# BB8_Head.net
KiCad netlist of a schematic drawn in EAGLE
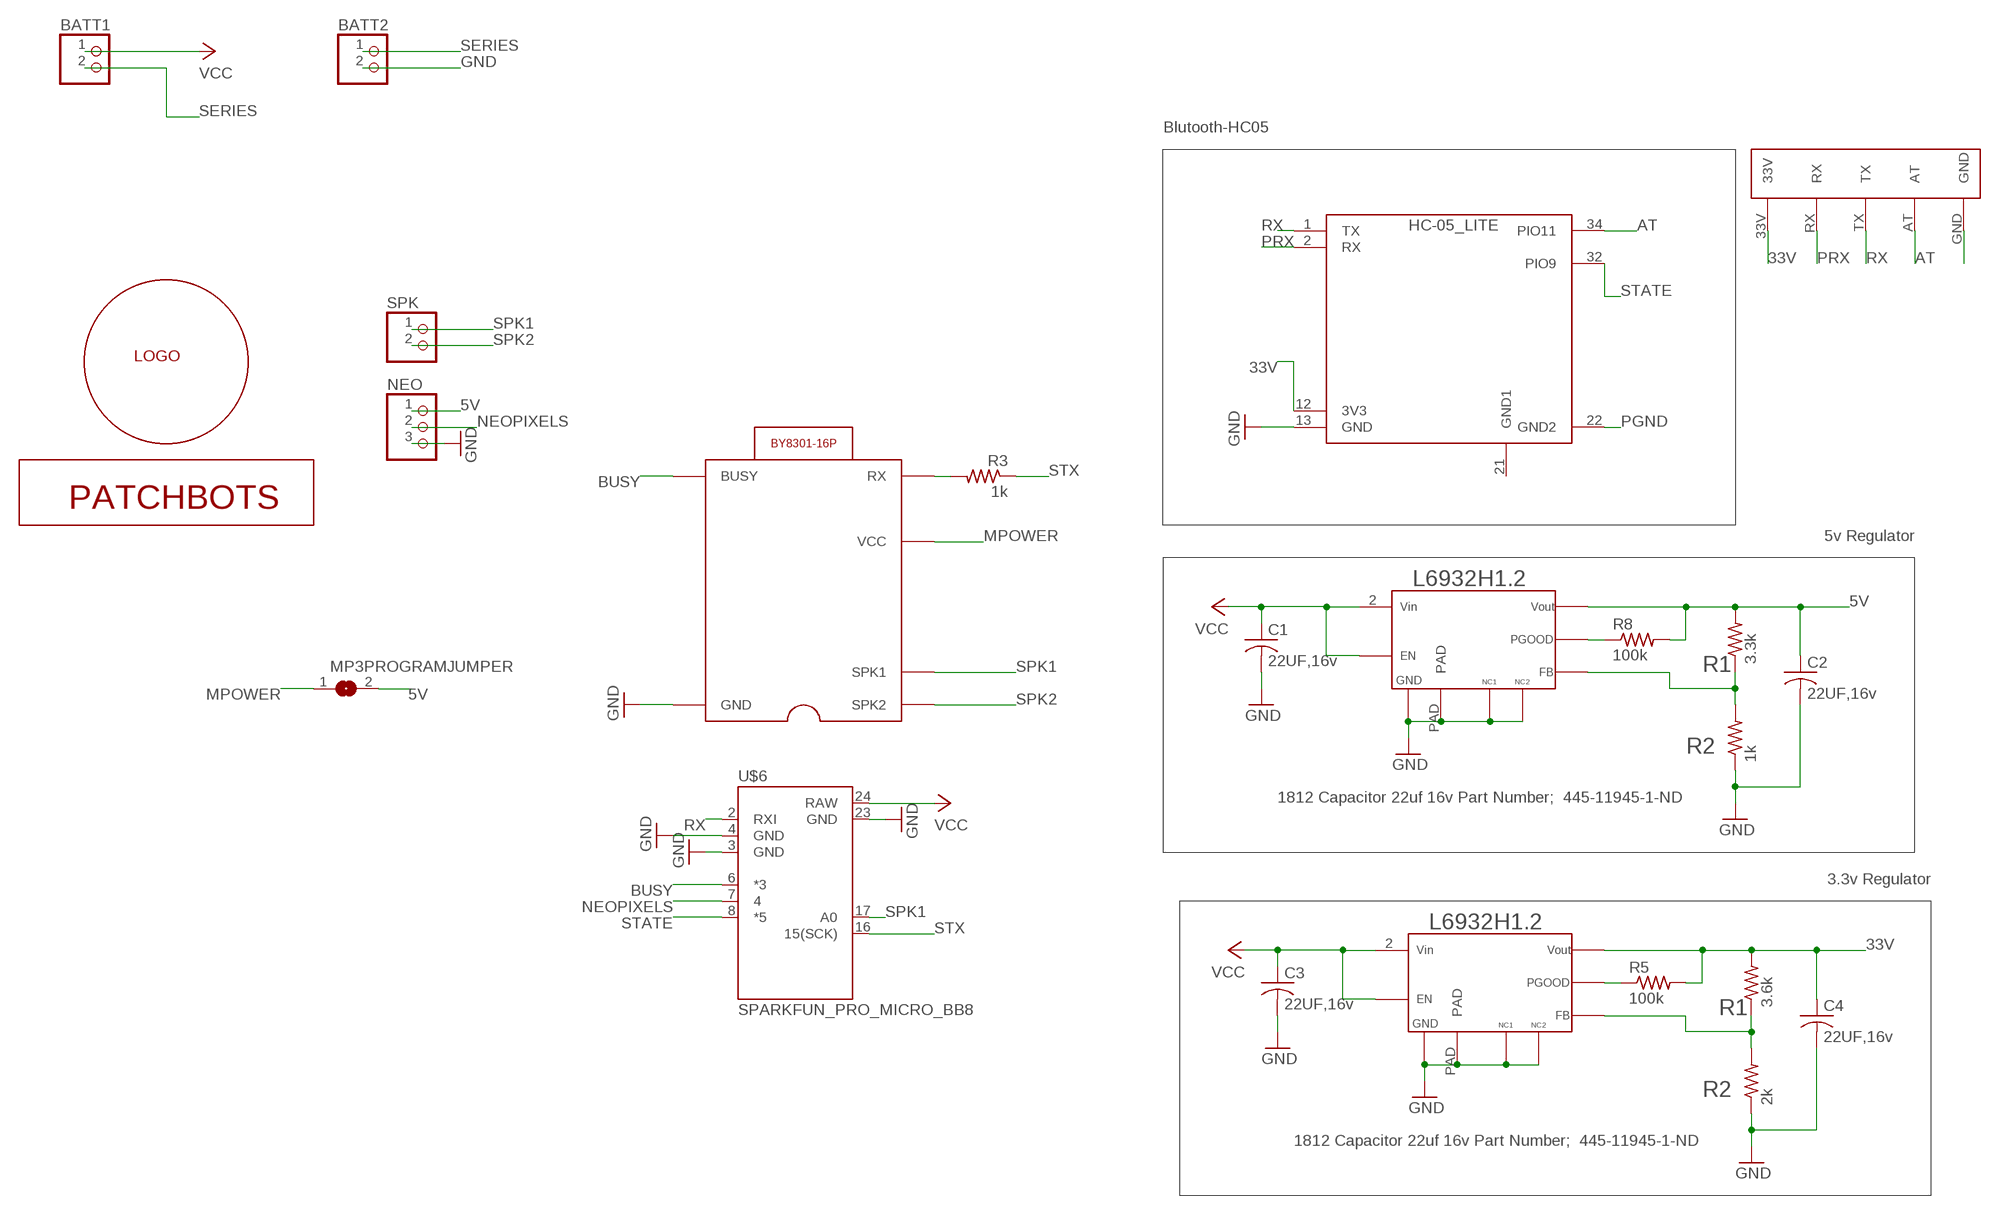
[diagram p0: schematic, sheet 1]

(export (version "E")
  (design (tool "Eeschema 10.0.6"))
  (components
    (comp (ref "BATT1")
      (value "PINHD-1X2")
      (footprint "eagle-import:1X02")
      (libsource (lib "eagle-import") (part "PINHD-1X2"))
    )
    (comp (ref "BATT2")
      (value "PINHD-1X2")
      (footprint "eagle-import:1X02")
      (libsource (lib "eagle-import") (part "PINHD-1X2"))
    )
    (comp (ref "C1")
      (value "22UF,16v")
      (footprint "eagle-import:C1812")
      (libsource (lib "eagle-import") (part "C-USC1812"))
    )
    (comp (ref "C2")
      (value "22UF,16v")
      (footprint "eagle-import:C1812")
      (libsource (lib "eagle-import") (part "C-USC1812"))
    )
    (comp (ref "C3")
      (value "22UF,16v")
      (footprint "eagle-import:C1812")
      (libsource (lib "eagle-import") (part "C-USC1812"))
    )
    (comp (ref "C4")
      (value "22UF,16v")
      (footprint "eagle-import:C1812")
      (libsource (lib "eagle-import") (part "C-USC1812"))
    )
    (comp (ref "HC-05")
      (value "HC-05_LITE")
      (footprint "eagle-import:BLUETOOTH_SMD_LITE")
      (libsource (lib "eagle-import") (part "HC-05_LITE"))
    )
    (comp (ref "MP3PROGRAMJUMPER")
      (value "SJ")
      (footprint "eagle-import:SJ")
      (libsource (lib "eagle-import") (part "SJ"))
    )
    (comp (ref "NEO")
      (value "PINHD-1X3")
      (footprint "eagle-import:1X03")
      (libsource (lib "eagle-import") (part "PINHD-1X3"))
    )
    (comp (ref "R1")
      (value "3.3k")
      (footprint "eagle-import:R2010")
      (libsource (lib "eagle-import") (part "R-US_R2010"))
    )
    (comp (ref "R3")
      (value "1k")
      (footprint "eagle-import:R2010")
      (libsource (lib "eagle-import") (part "R-US_R2010"))
    )
    (comp (ref "R5")
      (value "100k")
      (footprint "eagle-import:R2010")
      (libsource (lib "eagle-import") (part "R-US_R2010"))
    )
    (comp (ref "R6")
      (value "3.6k")
      (footprint "eagle-import:R2010")
      (libsource (lib "eagle-import") (part "R-US_R2010"))
    )
    (comp (ref "R7")
      (value "2k")
      (footprint "eagle-import:R2010")
      (libsource (lib "eagle-import") (part "R-US_R2010"))
    )
    (comp (ref "R8")
      (value "100k")
      (footprint "eagle-import:R2010")
      (libsource (lib "eagle-import") (part "R-US_R2010"))
    )
    (comp (ref "R9")
      (value "1k")
      (footprint "eagle-import:R2010")
      (libsource (lib "eagle-import") (part "R-US_R2010"))
    )
    (comp (ref "SPK")
      (value "PINHD-1X2")
      (footprint "eagle-import:1X02")
      (libsource (lib "eagle-import") (part "PINHD-1X2"))
    )
    (comp (ref "U$2")
      (value "LOGO_15MM-MIXED")
      (footprint "eagle-import:LOGO_15MM_MIXED")
      (libsource (lib "eagle-import") (part "LOGO_15MM-MIXED"))
    )
    (comp (ref "U$3")
      (value "L6932H1.2")
      (footprint "eagle-import:L6932H1")
      (libsource (lib "eagle-import") (part "L6932H1.2"))
    )
    (comp (ref "U$4")
      (value "PATCHBOTS_SPLIT15MM")
      (footprint "eagle-import:PATCHBOTS_SPLIT15MM")
      (libsource (lib "eagle-import") (part "PATCHBOTS_SPLIT15MM"))
    )
    (comp (ref "U$5")
      (value "L6932H1.2")
      (footprint "eagle-import:L6932H1")
      (libsource (lib "eagle-import") (part "L6932H1.2"))
    )
    (comp (ref "U$6")
      (value "SPARKFUN_PRO_MICRO_BB8")
      (footprint "eagle-import:SPARKFUN_PRO_MICRO_BB8")
      (libsource (lib "eagle-import") (part "SPARKFUN_PRO_MICRO_BB8"))
    )
    (comp (ref "U$7")
      (value "PROGRAMMER")
      (footprint "eagle-import:BLUETOOTH_SMD_PROGRAMMER")
      (libsource (lib "eagle-import") (part "PROGRAMMER"))
    )
    (comp (ref "U$8")
      (value "BY8301_BB8")
      (footprint "eagle-import:BY8301-16P_BB8")
      (libsource (lib "eagle-import") (part "BY8301_BB8"))
    )
  )
  (nets
    (net (code "1") (name "/AT") (class "Default")
      (node (ref "HC-05") (pin "34") (pinfunction "PIO11_34") (pintype "bidirectional"))
      (node (ref "U$7") (pin "AT") (pinfunction "AT_AT") (pintype "bidirectional"))
    )
    (net (code "2") (name "/MPOWER") (class "Default")
      (node (ref "MP3PROGRAMJUMPER") (pin "1") (pinfunction "1_1") (pintype "passive"))
      (node (ref "U$8") (pin "VCC") (pinfunction "VCC_VCC") (pintype "bidirectional"))
    )
    (net (code "3") (name "/PGND") (class "Default")
      (node (ref "HC-05") (pin "22") (pinfunction "GND2_22") (pintype "bidirectional"))
      (node (ref "U$7") (pin "GND") (pinfunction "GND_GND") (pintype "bidirectional"))
    )
    (net (code "4") (name "/PRX") (class "Default")
      (node (ref "HC-05") (pin "2") (pinfunction "RX_2") (pintype "bidirectional"))
      (node (ref "U$7") (pin "RX") (pinfunction "RX_RX") (pintype "bidirectional"))
    )
    (net (code "5") (name "5V") (class "Default")
      (node (ref "C2") (pin "1") (pinfunction "1_1") (pintype "passive"))
      (node (ref "MP3PROGRAMJUMPER") (pin "2") (pinfunction "2_2") (pintype "passive"))
      (node (ref "NEO") (pin "1") (pinfunction "1_1") (pintype "passive"))
      (node (ref "R1") (pin "2") (pinfunction "2_2") (pintype "passive"))
      (node (ref "R8") (pin "2") (pinfunction "2_2") (pintype "passive"))
      (node (ref "U$3") (pin "4") (pinfunction "4_4") (pintype "bidirectional"))
    )
    (net (code "6") (name "33V") (class "Default")
      (node (ref "C4") (pin "1") (pinfunction "1_1") (pintype "passive"))
      (node (ref "HC-05") (pin "12") (pinfunction "3V3_12") (pintype "bidirectional"))
      (node (ref "R5") (pin "2") (pinfunction "2_2") (pintype "passive"))
      (node (ref "R6") (pin "2") (pinfunction "2_2") (pintype "passive"))
      (node (ref "U$5") (pin "4") (pinfunction "4_4") (pintype "bidirectional"))
      (node (ref "U$7") (pin "33V") (pinfunction "33V_33V") (pintype "bidirectional"))
    )
    (net (code "7") (name "BUSY") (class "Default")
      (node (ref "U$6") (pin "6") (pinfunction "*3_6") (pintype "bidirectional"))
      (node (ref "U$8") (pin "BUSY") (pinfunction "BUSY_BUSY") (pintype "bidirectional"))
    )
    (net (code "8") (name "GND") (class "Default")
      (node (ref "BATT2") (pin "2") (pinfunction "2_2") (pintype "passive"))
      (node (ref "C1") (pin "2") (pinfunction "2_2") (pintype "passive"))
      (node (ref "C2") (pin "2") (pinfunction "2_2") (pintype "passive"))
      (node (ref "C3") (pin "2") (pinfunction "2_2") (pintype "passive"))
      (node (ref "C4") (pin "2") (pinfunction "2_2") (pintype "passive"))
      (node (ref "HC-05") (pin "13") (pinfunction "GND_13") (pintype "bidirectional"))
      (node (ref "NEO") (pin "3") (pinfunction "3_3") (pintype "passive"))
      (node (ref "R7") (pin "1") (pinfunction "1_1") (pintype "passive"))
      (node (ref "R9") (pin "1") (pinfunction "1_1") (pintype "passive"))
      (node (ref "U$3") (pin "6") (pinfunction "6_6") (pintype "bidirectional"))
      (node (ref "U$3") (pin "7") (pinfunction "7_7") (pintype "bidirectional"))
      (node (ref "U$3") (pin "8") (pinfunction "8_8") (pintype "bidirectional"))
      (node (ref "U$3") (pin "PAD") (pinfunction "PAD_PAD") (pintype "bidirectional"))
      (node (ref "U$5") (pin "6") (pinfunction "6_6") (pintype "bidirectional"))
      (node (ref "U$5") (pin "7") (pinfunction "7_7") (pintype "bidirectional"))
      (node (ref "U$5") (pin "8") (pinfunction "8_8") (pintype "bidirectional"))
      (node (ref "U$5") (pin "PAD") (pinfunction "PAD_PAD") (pintype "bidirectional"))
      (node (ref "U$6") (pin "23") (pinfunction "GND_23") (pintype "power_in"))
      (node (ref "U$6") (pin "3") (pinfunction "GND_3") (pintype "power_in"))
      (node (ref "U$6") (pin "4") (pinfunction "GND_4") (pintype "power_in"))
      (node (ref "U$8") (pin "GND") (pinfunction "GND_GND") (pintype "bidirectional"))
    )
    (net (code "9") (name "NEOPIXELS") (class "Default")
      (node (ref "NEO") (pin "2") (pinfunction "2_2") (pintype "passive"))
      (node (ref "U$6") (pin "7") (pinfunction "4_7") (pintype "bidirectional"))
    )
    (net (code "10") (name "Net-(R1-Pad1)") (class "Default")
      (node (ref "R1") (pin "1") (pinfunction "1_1") (pintype "passive"))
      (node (ref "R9") (pin "2") (pinfunction "2_2") (pintype "passive"))
      (node (ref "U$3") (pin "3") (pinfunction "3_3") (pintype "bidirectional"))
    )
    (net (code "11") (name "Net-(R3-Pad2)") (class "Default")
      (node (ref "R3") (pin "2") (pinfunction "2_2") (pintype "passive"))
      (node (ref "U$8") (pin "RX") (pinfunction "RX_RX") (pintype "bidirectional"))
    )
    (net (code "12") (name "Net-(R5-Pad1)") (class "Default")
      (node (ref "R5") (pin "1") (pinfunction "1_1") (pintype "passive"))
      (node (ref "U$5") (pin "5") (pinfunction "5_5") (pintype "bidirectional"))
    )
    (net (code "13") (name "Net-(R6-Pad1)") (class "Default")
      (node (ref "R6") (pin "1") (pinfunction "1_1") (pintype "passive"))
      (node (ref "R7") (pin "2") (pinfunction "2_2") (pintype "passive"))
      (node (ref "U$5") (pin "3") (pinfunction "3_3") (pintype "bidirectional"))
    )
    (net (code "14") (name "Net-(R8-Pad1)") (class "Default")
      (node (ref "R8") (pin "1") (pinfunction "1_1") (pintype "passive"))
      (node (ref "U$3") (pin "5") (pinfunction "5_5") (pintype "bidirectional"))
    )
    (net (code "15") (name "RX") (class "Default")
      (node (ref "HC-05") (pin "1") (pinfunction "TX_1") (pintype "bidirectional"))
      (node (ref "U$6") (pin "2") (pinfunction "RXI_2") (pintype "bidirectional"))
      (node (ref "U$7") (pin "TX") (pinfunction "TX_TX") (pintype "bidirectional"))
    )
    (net (code "16") (name "SERIES") (class "Default")
      (node (ref "BATT1") (pin "2") (pinfunction "2_2") (pintype "passive"))
      (node (ref "BATT2") (pin "1") (pinfunction "1_1") (pintype "passive"))
    )
    (net (code "17") (name "SPK1") (class "Default")
      (node (ref "SPK") (pin "1") (pinfunction "1_1") (pintype "passive"))
      (node (ref "U$6") (pin "17") (pinfunction "A0_17") (pintype "bidirectional"))
      (node (ref "U$8") (pin "SPK1") (pinfunction "SPK1_SPK1") (pintype "bidirectional"))
    )
    (net (code "18") (name "SPK2") (class "Default")
      (node (ref "SPK") (pin "2") (pinfunction "2_2") (pintype "passive"))
      (node (ref "U$8") (pin "SPK2") (pinfunction "SPK2_SPK2") (pintype "bidirectional"))
    )
    (net (code "19") (name "STATE") (class "Default")
      (node (ref "HC-05") (pin "32") (pinfunction "PIO9_32") (pintype "bidirectional"))
      (node (ref "U$6") (pin "8") (pinfunction "*5_8") (pintype "bidirectional"))
    )
    (net (code "20") (name "STX") (class "Default")
      (node (ref "R3") (pin "1") (pinfunction "1_1") (pintype "passive"))
      (node (ref "U$6") (pin "16") (pinfunction "15(SCK)_16") (pintype "bidirectional"))
    )
    (net (code "21") (name "VCC") (class "Default")
      (node (ref "BATT1") (pin "1") (pinfunction "1_1") (pintype "passive"))
      (node (ref "C1") (pin "1") (pinfunction "1_1") (pintype "passive"))
      (node (ref "C3") (pin "1") (pinfunction "1_1") (pintype "passive"))
      (node (ref "U$3") (pin "1") (pinfunction "1_1") (pintype "bidirectional"))
      (node (ref "U$3") (pin "2") (pinfunction "2_2") (pintype "bidirectional"))
      (node (ref "U$5") (pin "1") (pinfunction "1_1") (pintype "bidirectional"))
      (node (ref "U$5") (pin "2") (pinfunction "2_2") (pintype "bidirectional"))
      (node (ref "U$6") (pin "24") (pinfunction "RAW_24") (pintype "power_in"))
    )
    (net (code "22") (name "unconnected-(HC-05-GND1-Pad21)") (class "Default")
      (node (ref "HC-05") (pin "21") (pinfunction "GND1_21") (pintype "bidirectional"))
    )
  )
)
